# power_mux-v12.net
KiCad netlist of a schematic drawn in EAGLE
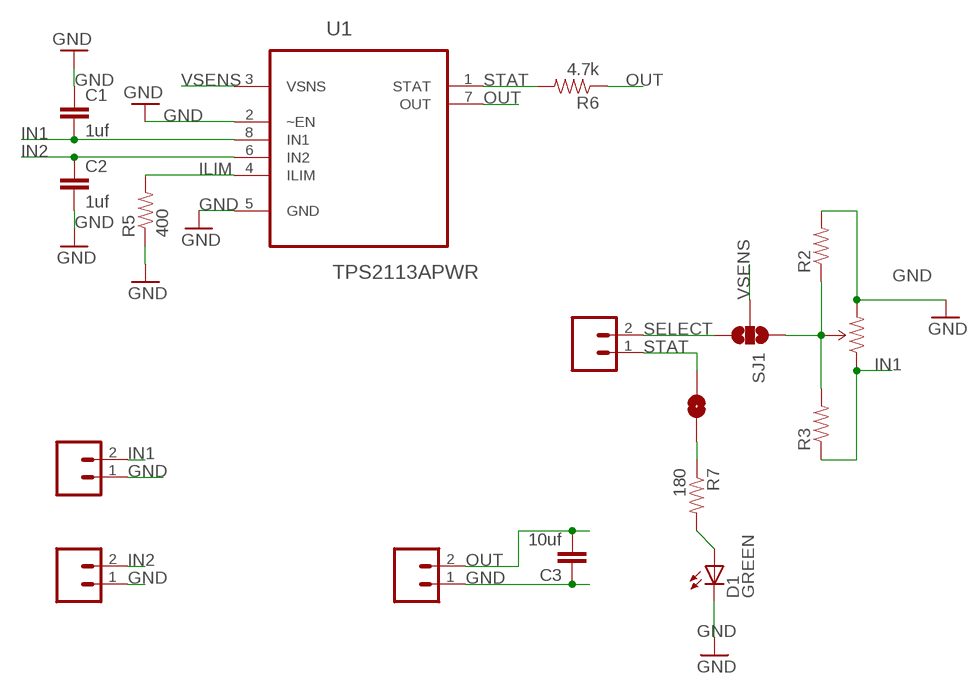
[diagram p0: schematic, sheet 1]

(export (version "E")
  (design (tool "Eeschema 10.0.6"))
  (components
    (comp (ref "C1")
      (value "1uf")
      (footprint "eagle-import:0603-CAP")
      (libsource (lib "eagle-import") (part "SparkFun-Passives_CAP0603-CAP"))
    )
    (comp (ref "C2")
      (value "1uf")
      (footprint "eagle-import:0603-CAP")
      (libsource (lib "eagle-import") (part "SparkFun-Passives_CAP0603-CAP"))
    )
    (comp (ref "C3")
      (value "10uf")
      (footprint "eagle-import:0603-CAP")
      (libsource (lib "eagle-import") (part "CAP0603-CAP"))
    )
    (comp (ref "D1")
      (value "GREEN")
      (footprint "eagle-import:LED-0603")
      (libsource (lib "eagle-import") (part "LED-GREEN0603"))
    )
    (comp (ref "JP3")
      (value "M021X02_NO_SILK")
      (footprint "eagle-import:1X02_NO_SILK")
      (libsource (lib "eagle-import") (part "M021X02_NO_SILK"))
    )
    (comp (ref "JP4")
      (value "M021X02_NO_SILK")
      (footprint "eagle-import:1X02_NO_SILK")
      (libsource (lib "eagle-import") (part "M021X02_NO_SILK"))
    )
    (comp (ref "JP5")
      (value "M021X02_NO_SILK")
      (footprint "eagle-import:1X02_NO_SILK")
      (libsource (lib "eagle-import") (part "M021X02_NO_SILK"))
    )
    (comp (ref "JP6")
      (value "M021X02_NO_SILK")
      (footprint "eagle-import:1X02_NO_SILK")
      (libsource (lib "eagle-import") (part "M021X02_NO_SILK"))
    )
    (comp (ref "R1")
      (value "TRIMPOT-PTH-KNOB")
      (footprint "eagle-import:3386U")
      (libsource (lib "eagle-import") (part "TRIMPOT-PTH-KNOB"))
    )
    (comp (ref "R2")
      (value "RESISTOR0603")
      (footprint "eagle-import:0603-RES")
      (libsource (lib "eagle-import") (part "RESISTOR0603"))
    )
    (comp (ref "R3")
      (value "RESISTOR0603")
      (footprint "eagle-import:0603-RES")
      (libsource (lib "eagle-import") (part "RESISTOR0603"))
    )
    (comp (ref "R5")
      (value "400")
      (footprint "eagle-import:0603-RES")
      (libsource (lib "eagle-import") (part "RESISTOR0603-RES"))
    )
    (comp (ref "R6")
      (value "4.7k")
      (footprint "eagle-import:0603-RES")
      (libsource (lib "eagle-import") (part "RESISTOR0603-RES"))
    )
    (comp (ref "R7")
      (value "180")
      (footprint "eagle-import:0603-RES")
      (libsource (lib "eagle-import") (part "RESISTOR0603-RES"))
    )
    (comp (ref "SJ1")
      (value "SOLDERJUMPER_2WAYPASTE1&2")
      (footprint "eagle-import:SJ_3_PASTE1&2")
      (libsource (lib "eagle-import") (part "SOLDERJUMPER_2WAYPASTE1&2"))
    )
    (comp (ref "SJ2")
      (value "SOLDERJUMPERNC2")
      (footprint "eagle-import:SJ_2S-NOTRACE")
      (libsource (lib "eagle-import") (part "SOLDERJUMPERNC2"))
    )
    (comp (ref "U1")
      (value "TPS2113APWR")
      (footprint "eagle-import:SOP65P640X120-8N")
      (libsource (lib "eagle-import") (part "TPS2113APWR"))
    )
  )
  (nets
    (net (code "1") (name "/ILIM") (class "Default")
      (node (ref "R5") (pin "2") (pinfunction "2_2") (pintype "passive"))
      (node (ref "U1") (pin "4") (pinfunction "ILIM_4") (pintype "input"))
    )
    (net (code "2") (name "/IN1") (class "Default")
      (node (ref "C1") (pin "2") (pinfunction "2_2") (pintype "passive"))
      (node (ref "JP3") (pin "2") (pinfunction "2_2") (pintype "passive"))
      (node (ref "R1") (pin "1") (pinfunction "CCW_1") (pintype "passive"))
      (node (ref "R3") (pin "1") (pinfunction "1_1") (pintype "passive"))
      (node (ref "U1") (pin "8") (pinfunction "IN1_8") (pintype "input"))
    )
    (net (code "3") (name "/IN2") (class "Default")
      (node (ref "C2") (pin "1") (pinfunction "1_1") (pintype "passive"))
      (node (ref "JP4") (pin "2") (pinfunction "2_2") (pintype "passive"))
      (node (ref "U1") (pin "6") (pinfunction "IN2_6") (pintype "input"))
    )
    (net (code "4") (name "/OUT") (class "Default")
      (node (ref "C3") (pin "2") (pinfunction "2_2") (pintype "passive"))
      (node (ref "JP6") (pin "2") (pinfunction "2_2") (pintype "passive"))
      (node (ref "R6") (pin "1") (pinfunction "1_1") (pintype "passive"))
      (node (ref "U1") (pin "7") (pinfunction "OUT_7") (pintype "output"))
    )
    (net (code "5") (name "/SELECT") (class "Default")
      (node (ref "JP5") (pin "2") (pinfunction "2_2") (pintype "passive"))
      (node (ref "SJ1") (pin "3") (pinfunction "3_3") (pintype "passive"))
    )
    (net (code "6") (name "/STAT") (class "Default")
      (node (ref "JP5") (pin "1") (pinfunction "1_1") (pintype "passive"))
      (node (ref "R6") (pin "2") (pinfunction "2_2") (pintype "passive"))
      (node (ref "SJ2") (pin "2") (pinfunction "2_2") (pintype "passive"))
      (node (ref "U1") (pin "1") (pinfunction "STAT_1") (pintype "output"))
    )
    (net (code "7") (name "/VSENS") (class "Default")
      (node (ref "SJ1") (pin "2") (pinfunction "2_2") (pintype "passive"))
      (node (ref "U1") (pin "3") (pinfunction "VSNS_3") (pintype "power_in"))
    )
    (net (code "8") (name "GND") (class "Default")
      (node (ref "C1") (pin "1") (pinfunction "1_1") (pintype "passive"))
      (node (ref "C2") (pin "2") (pinfunction "2_2") (pintype "passive"))
      (node (ref "C3") (pin "1") (pinfunction "1_1") (pintype "passive"))
      (node (ref "D1") (pin "C") (pinfunction "C_C") (pintype "passive"))
      (node (ref "JP3") (pin "1") (pinfunction "1_1") (pintype "passive"))
      (node (ref "JP4") (pin "1") (pinfunction "1_1") (pintype "passive"))
      (node (ref "JP6") (pin "1") (pinfunction "1_1") (pintype "passive"))
      (node (ref "R1") (pin "3") (pinfunction "CW_3") (pintype "passive"))
      (node (ref "R2") (pin "2") (pinfunction "2_2") (pintype "passive"))
      (node (ref "R5") (pin "1") (pinfunction "1_1") (pintype "passive"))
      (node (ref "U1") (pin "2") (pinfunction "~{EN}_2") (pintype "input"))
      (node (ref "U1") (pin "5") (pinfunction "GND_5") (pintype "passive"))
    )
    (net (code "9") (name "Net-(D1-PadA)") (class "Default")
      (node (ref "D1") (pin "A") (pinfunction "A_A") (pintype "passive"))
      (node (ref "R7") (pin "2") (pinfunction "2_2") (pintype "passive"))
    )
    (net (code "10") (name "Net-(R1-WIPER)") (class "Default")
      (node (ref "R1") (pin "2") (pinfunction "WIPER_2") (pintype "passive"))
      (node (ref "R2") (pin "1") (pinfunction "1_1") (pintype "passive"))
      (node (ref "R3") (pin "2") (pinfunction "2_2") (pintype "passive"))
      (node (ref "SJ1") (pin "1") (pinfunction "1_1") (pintype "passive"))
    )
    (net (code "11") (name "Net-(R7-Pad1)") (class "Default")
      (node (ref "R7") (pin "1") (pinfunction "1_1") (pintype "passive"))
      (node (ref "SJ2") (pin "1") (pinfunction "1_1") (pintype "passive"))
    )
  )
)
